# buttons.net
KiCad netlist of a schematic drawn in Altium Designer
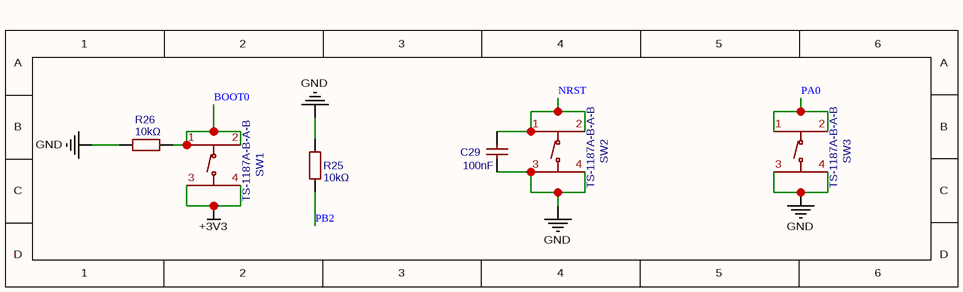
[diagram p0: buttons.schdoc]

(export (version "E")
  (design (tool "Eeschema 10.0.6"))
  (components
    (comp (ref "C29")
      (value "100nF")
      (fields
        (field (name "MANUFACTURER PART") "CL05B104KO5NNNC")
        (field (name "MANUFACTURER") "SAMSUNG(三星)")
      )
      (libsource (lib "altium-import") (part "root_3_100nF_"))
    )
    (comp (ref "R25")
      (value "10kΩ")
      (fields
        (field (name "MANUFACTURER") "UNI-ROYAL(厚声)")
        (field (name "MANUFACTURER PART") "0402WGF1002TCE")
      )
      (libsource (lib "altium-import") (part "root_3_10kΩ_"))
    )
    (comp (ref "R26")
      (value "10kΩ")
      (fields
        (field (name "MANUFACTURER") "UNI-ROYAL(厚声)")
        (field (name "MANUFACTURER PART") "0402WGF1002TCE")
      )
      (libsource (lib "altium-import") (part "root_2_10kΩ_"))
    )
    (comp (ref "SW1")
      (value "TS-1187A-B-A-B")
      (fields (field (name "MANUFACTURER") "XKB Connectivity(中国星坤)") (field (name "CONTRIBUTOR") "LCSC"))
      (libsource (lib "altium-import") (part "root_0_TS-1187A-B-A-B_"))
    )
    (comp (ref "SW2")
      (value "TS-1187A-B-A-B")
      (fields (field (name "MANUFACTURER") "XKB Connectivity(中国星坤)") (field (name "CONTRIBUTOR") "LCSC"))
      (libsource (lib "altium-import") (part "root_0_TS-1187A-B-A-B_"))
    )
    (comp (ref "SW3")
      (value "TS-1187A-B-A-B")
      (fields (field (name "MANUFACTURER") "XKB Connectivity(中国星坤)") (field (name "CONTRIBUTOR") "LCSC"))
      (libsource (lib "altium-import") (part "root_0_TS-1187A-B-A-B_"))
    )
  )
  (nets
    (net (code "1") (name "+3V3") (class "Default")
      (node (ref "SW1") (pin "3") (pinfunction "C_3") (pintype "passive"))
      (node (ref "SW1") (pin "4") (pinfunction "D_4") (pintype "passive"))
    )
    (net (code "2") (name "/BOOT0") (class "Default")
      (node (ref "R26") (pin "1") (pinfunction "1_1") (pintype "passive"))
      (node (ref "SW1") (pin "1") (pinfunction "A_1") (pintype "passive"))
      (node (ref "SW1") (pin "2") (pinfunction "B_2") (pintype "passive"))
    )
    (net (code "3") (name "/NRST") (class "Default")
      (node (ref "C29") (pin "2") (pinfunction "2_2") (pintype "passive"))
      (node (ref "SW2") (pin "1") (pinfunction "A_1") (pintype "passive"))
      (node (ref "SW2") (pin "2") (pinfunction "B_2") (pintype "passive"))
    )
    (net (code "4") (name "/PA0") (class "Default")
      (node (ref "SW3") (pin "1") (pinfunction "A_1") (pintype "passive"))
      (node (ref "SW3") (pin "2") (pinfunction "B_2") (pintype "passive"))
    )
    (net (code "5") (name "/PB2") (class "Default")
      (node (ref "R25") (pin "2") (pinfunction "2_2") (pintype "passive"))
    )
    (net (code "6") (name "GND") (class "Default")
      (node (ref "C29") (pin "1") (pinfunction "1_1") (pintype "passive"))
      (node (ref "R25") (pin "1") (pinfunction "1_1") (pintype "passive"))
      (node (ref "R26") (pin "2") (pinfunction "2_2") (pintype "passive"))
      (node (ref "SW2") (pin "3") (pinfunction "C_3") (pintype "passive"))
      (node (ref "SW2") (pin "4") (pinfunction "D_4") (pintype "passive"))
      (node (ref "SW3") (pin "3") (pinfunction "C_3") (pintype "passive"))
      (node (ref "SW3") (pin "4") (pinfunction "D_4") (pintype "passive"))
    )
  )
)
